# stm32f103c8t6.net
KiCad netlist of a schematic drawn in EasyEDA Pro
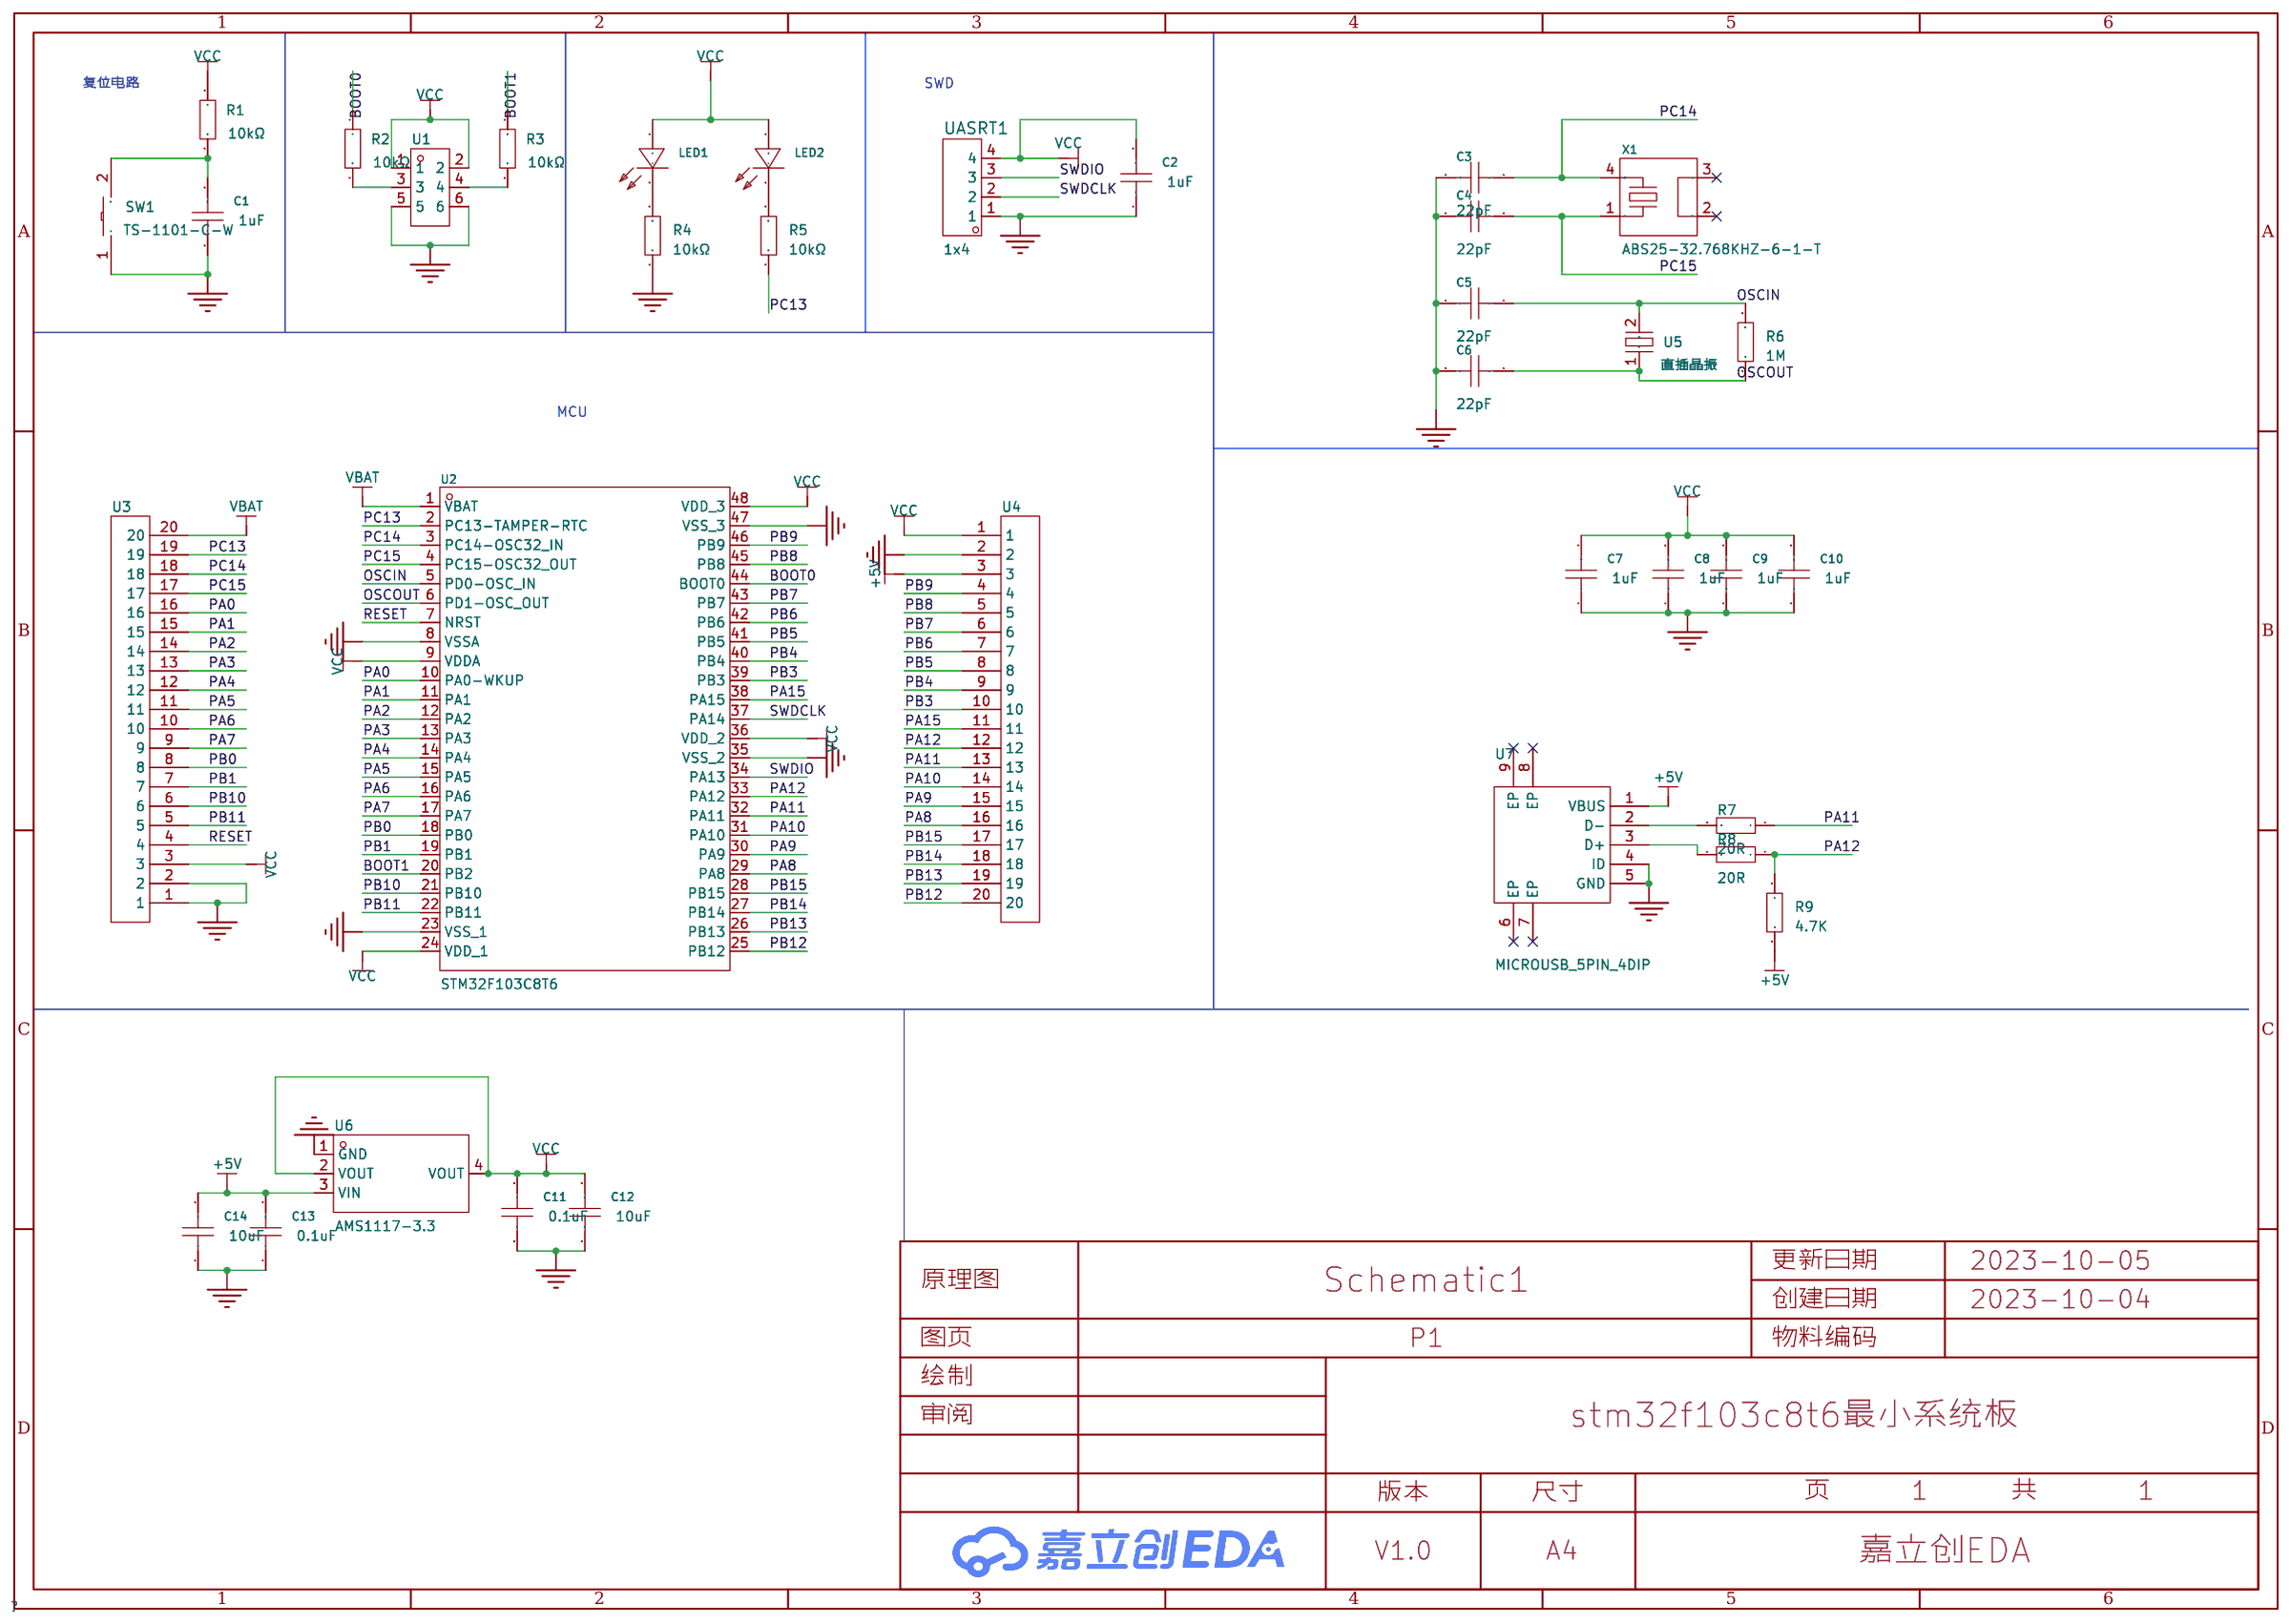
[diagram p0: schematic sheet]

(export (version "E")
  (design (tool "Eeschema 10.0.6"))
  (components
    (comp (ref "C1")
      (value "1uF")
      (footprint "easyedapro:C0603")
      (description "容值:4.7uF;额定电压:25V;材质(温度系数):X5R;")
      (fields
        (field (name "Manufacturer Part") "TCC0603X5R475K250CT")
        (field (name "Manufacturer") "CCTC(三环)")
      )
      (libsource (lib "easyedapro") (part "TCC0603X5R475K250CT"))
    )
    (comp (ref "C2")
      (value "1uF")
      (footprint "easyedapro:C0603")
      (description "容值:4.7uF;额定电压:25V;材质(温度系数):X5R;")
      (fields
        (field (name "Manufacturer Part") "TCC0603X5R475K250CT")
        (field (name "Manufacturer") "CCTC(三环)")
      )
      (libsource (lib "easyedapro") (part "TCC0603X5R475K250CT"))
    )
    (comp (ref "C3")
      (value "22pF")
      (footprint "easyedapro:C0603")
      (description "容值:4.7uF;额定电压:25V;材质(温度系数):X5R;")
      (fields
        (field (name "Manufacturer Part") "TCC0603X5R475K250CT")
        (field (name "Manufacturer") "CCTC(三环)")
      )
      (libsource (lib "easyedapro") (part "TCC0603X5R475K250CT"))
    )
    (comp (ref "C4")
      (value "22pF")
      (footprint "easyedapro:C0603")
      (description "容值:4.7uF;额定电压:25V;材质(温度系数):X5R;")
      (fields
        (field (name "Manufacturer Part") "TCC0603X5R475K250CT")
        (field (name "Manufacturer") "CCTC(三环)")
      )
      (libsource (lib "easyedapro") (part "TCC0603X5R475K250CT"))
    )
    (comp (ref "C5")
      (value "22pF")
      (footprint "easyedapro:C0603")
      (description "容值:4.7uF;额定电压:25V;材质(温度系数):X5R;")
      (fields
        (field (name "Manufacturer Part") "TCC0603X5R475K250CT")
        (field (name "Manufacturer") "CCTC(三环)")
      )
      (libsource (lib "easyedapro") (part "TCC0603X5R475K250CT"))
    )
    (comp (ref "C6")
      (value "22pF")
      (footprint "easyedapro:C0603")
      (description "容值:4.7uF;额定电压:25V;材质(温度系数):X5R;")
      (fields
        (field (name "Manufacturer Part") "TCC0603X5R475K250CT")
        (field (name "Manufacturer") "CCTC(三环)")
      )
      (libsource (lib "easyedapro") (part "TCC0603X5R475K250CT"))
    )
    (comp (ref "C7")
      (value "1uF")
      (footprint "easyedapro:C0603")
      (description "容值:4.7uF;额定电压:25V;材质(温度系数):X5R;")
      (fields
        (field (name "Manufacturer Part") "TCC0603X5R475K250CT")
        (field (name "Manufacturer") "CCTC(三环)")
      )
      (libsource (lib "easyedapro") (part "TCC0603X5R475K250CT"))
    )
    (comp (ref "C8")
      (value "1uF")
      (footprint "easyedapro:C0603")
      (description "容值:4.7uF;额定电压:25V;材质(温度系数):X5R;")
      (fields
        (field (name "Manufacturer Part") "TCC0603X5R475K250CT")
        (field (name "Manufacturer") "CCTC(三环)")
      )
      (libsource (lib "easyedapro") (part "TCC0603X5R475K250CT"))
    )
    (comp (ref "C9")
      (value "1uF")
      (footprint "easyedapro:C0603")
      (description "容值:4.7uF;额定电压:25V;材质(温度系数):X5R;")
      (fields
        (field (name "Manufacturer Part") "TCC0603X5R475K250CT")
        (field (name "Manufacturer") "CCTC(三环)")
      )
      (libsource (lib "easyedapro") (part "TCC0603X5R475K250CT"))
    )
    (comp (ref "C10")
      (value "1uF")
      (footprint "easyedapro:C0603")
      (description "容值:4.7uF;额定电压:25V;材质(温度系数):X5R;")
      (fields
        (field (name "Manufacturer Part") "TCC0603X5R475K250CT")
        (field (name "Manufacturer") "CCTC(三环)")
      )
      (libsource (lib "easyedapro") (part "TCC0603X5R475K250CT"))
    )
    (comp (ref "C11")
      (value "0.1uF")
      (footprint "easyedapro:C0603")
      (description "容值:4.7uF;额定电压:25V;材质(温度系数):X5R;")
      (fields
        (field (name "Manufacturer Part") "TCC0603X5R475K250CT")
        (field (name "Manufacturer") "CCTC(三环)")
      )
      (libsource (lib "easyedapro") (part "TCC0603X5R475K250CT"))
    )
    (comp (ref "C12")
      (value "10uF")
      (footprint "easyedapro:C0603")
      (description "容值:4.7uF;额定电压:25V;材质(温度系数):X5R;")
      (fields
        (field (name "Manufacturer Part") "TCC0603X5R475K250CT")
        (field (name "Manufacturer") "CCTC(三环)")
      )
      (libsource (lib "easyedapro") (part "TCC0603X5R475K250CT"))
    )
    (comp (ref "C13")
      (value "0.1uF")
      (footprint "easyedapro:C0603")
      (description "容值:4.7uF;额定电压:25V;材质(温度系数):X5R;")
      (fields
        (field (name "Manufacturer Part") "TCC0603X5R475K250CT")
        (field (name "Manufacturer") "CCTC(三环)")
      )
      (libsource (lib "easyedapro") (part "TCC0603X5R475K250CT"))
    )
    (comp (ref "C14")
      (value "10uF")
      (footprint "easyedapro:C0603")
      (description "容值:4.7uF;额定电压:25V;材质(温度系数):X5R;")
      (fields
        (field (name "Manufacturer Part") "TCC0603X5R475K250CT")
        (field (name "Manufacturer") "CCTC(三环)")
      )
      (libsource (lib "easyedapro") (part "TCC0603X5R475K250CT"))
    )
    (comp (ref "LED1")
      (value "KT-0805G")
      (footprint "easyedapro:LED0805-R-RD")
      (description "发光颜色:翠绿;二极管配置:-;透镜颜色:-;主波长:-;色温:-;光通量(25℃时):-;发光强度:-;功率:-;发光角度:-;安装方式:-;工作温度:-;")
      (fields (field (name "Manufacturer") "KENTO"))
      (libsource (lib "easyedapro") (part "0805G (Green)"))
    )
    (comp (ref "LED2")
      (value "KT-0805G")
      (footprint "easyedapro:LED0805-R-RD")
      (description "发光颜色:翠绿;二极管配置:-;透镜颜色:-;主波长:-;色温:-;光通量(25°C时):-;发光强度:-;功率:-;发光角度:-;安装方式:-;工作温度:-;")
      (fields (field (name "Manufacturer") "KENTO"))
      (libsource (lib "easyedapro") (part "0805G (Green)"))
    )
    (comp (ref "R1")
      (value "10kΩ")
      (footprint "easyedapro:R0603")
      (description "电阻类型:厚膜电阻;阻值:10kΩ;精度:±1%;功率:100mW;")
      (fields
        (field (name "Manufacturer Part") "0603WAF1002T5E")
        (field (name "Manufacturer") "UNI-ROYAL(厚声)")
      )
      (libsource (lib "easyedapro") (part "0603WAF1002T5E"))
    )
    (comp (ref "R2")
      (value "10kΩ")
      (footprint "easyedapro:R0603")
      (description "电阻类型:厚膜电阻;阻值:10kΩ;精度:±1%;功率:100mW;")
      (fields
        (field (name "Manufacturer Part") "0603WAF1002T5E")
        (field (name "Manufacturer") "UNI-ROYAL(厚声)")
      )
      (libsource (lib "easyedapro") (part "0603WAF1002T5E"))
    )
    (comp (ref "R3")
      (value "10kΩ")
      (footprint "easyedapro:R0603")
      (description "电阻类型:厚膜电阻;阻值:10kΩ;精度:±1%;功率:100mW;")
      (fields
        (field (name "Manufacturer Part") "0603WAF1002T5E")
        (field (name "Manufacturer") "UNI-ROYAL(厚声)")
      )
      (libsource (lib "easyedapro") (part "0603WAF1002T5E"))
    )
    (comp (ref "R4")
      (value "10kΩ")
      (footprint "easyedapro:R0603")
      (description "电阻类型:厚膜电阻;阻值:10kΩ;精度:±1%;功率:100mW;")
      (fields
        (field (name "Manufacturer Part") "0603WAF1002T5E")
        (field (name "Manufacturer") "UNI-ROYAL(厚声)")
      )
      (libsource (lib "easyedapro") (part "0603WAF1002T5E"))
    )
    (comp (ref "R5")
      (value "10kΩ")
      (footprint "easyedapro:R0603")
      (description "电阻类型:厚膜电阻;阻值:10kΩ;精度:±1%;功率:100mW;")
      (fields
        (field (name "Manufacturer Part") "0603WAF1002T5E")
        (field (name "Manufacturer") "UNI-ROYAL(厚声)")
      )
      (libsource (lib "easyedapro") (part "0603WAF1002T5E"))
    )
    (comp (ref "R6")
      (value "1M")
      (footprint "easyedapro:R0603")
      (description "电阻类型:厚膜电阻;阻值:10kΩ;精度:±1%;功率:100mW;")
      (fields
        (field (name "Manufacturer Part") "0603WAF1002T5E")
        (field (name "Manufacturer") "UNI-ROYAL(厚声)")
      )
      (libsource (lib "easyedapro") (part "0603WAF1002T5E"))
    )
    (comp (ref "R7")
      (value "20R")
      (footprint "easyedapro:R0603")
      (description "电阻类型:厚膜电阻;阻值:10kΩ;精度:±1%;功率:100mW;")
      (fields
        (field (name "Manufacturer Part") "0603WAF1002T5E")
        (field (name "Manufacturer") "UNI-ROYAL(厚声)")
      )
      (libsource (lib "easyedapro") (part "0603WAF1002T5E"))
    )
    (comp (ref "R8")
      (value "20R")
      (footprint "easyedapro:R0603")
      (description "电阻类型:厚膜电阻;阻值:10kΩ;精度:±1%;功率:100mW;")
      (fields
        (field (name "Manufacturer Part") "0603WAF1002T5E")
        (field (name "Manufacturer") "UNI-ROYAL(厚声)")
      )
      (libsource (lib "easyedapro") (part "0603WAF1002T5E"))
    )
    (comp (ref "R9")
      (value "4.7K")
      (footprint "easyedapro:R0603")
      (description "电阻类型:厚膜电阻;阻值:10kΩ;精度:±1%;功率:100mW;")
      (fields
        (field (name "Manufacturer Part") "0603WAF1002T5E")
        (field (name "Manufacturer") "UNI-ROYAL(厚声)")
      )
      (libsource (lib "easyedapro") (part "0603WAF1002T5E"))
    )
    (comp (ref "SW1")
      (value "TS-1101-C-W")
      (footprint "easyedapro:SW-SMD_L6.0-W3.3-LS8.0")
      (description "触点电流:50mA;额定电压(AC):-;额定电压(DC):12V;额定功率:-;绝缘电阻:-;电路结构:单刀单掷;安装方式:立贴;带灯:无;作用力:260gf;机械寿命:5万次;带支架:否;")
      (fields (field (name "Manufacturer") "XKB Connectivity(中国星坤)"))
      (libsource (lib "easyedapro") (part "TS-1101-C-W"))
    )
    (comp (ref "U1")
      (value "2.54mm,2X3,短针针长3mm,长针针长6mm")
      (footprint "easyedapro:HDR-TH_6P-P2.54-V-M-R2-C3-S2.54-2")
      (libsource (lib "easyedapro") (part "2.54MM,2X3,短针针长3MM,长针针长6MM"))
    )
    (comp (ref "U2")
      (value "STM32F103C8T6")
      (footprint "easyedapro:LQFP-48_L7.0-W7.0-P0.50-LS9.0-BL")
      (fields (field (name "Manufacturer") "ST(意法半导体)"))
      (libsource (lib "easyedapro") (part "STM32F103C8T6"))
    )
    (comp (ref "U3")
      (value "~")
      (footprint "easyedapro:HDR1X20")
      (libsource (lib "easyedapro") (part "1X20"))
    )
    (comp (ref "U4")
      (value "~")
      (footprint "easyedapro:HDR1X20")
      (libsource (lib "easyedapro") (part "1X20"))
    )
    (comp (ref "U5")
      (value "直插晶振")
      (footprint "easyedapro:HC-49S_L11.0-W4.7-P4.88")
      (libsource (lib "easyedapro") (part "直插晶振"))
    )
    (comp (ref "U6")
      (value "AMS1117-3.3")
      (footprint "easyedapro:SOT-223-3_L6.5-W3.4-P2.30-LS7.0-BR")
      (description "输出类型:固定;输出极性:正;最大输入电压:-;输出电压:3.3V;输出电流:1A;电源纹波抑制比(PSRR):72dB@(120Hz);")
      (fields (field (name "Manufacturer") "AMS"))
      (libsource (lib "easyedapro") (part "AMS1117-3.3"))
    )
    (comp (ref "U7")
      (value "MICROUSB_5PIN_4DIP")
      (footprint "easyedapro:MICRO-USB-SMD_U254-051N-4BH806")
      (libsource (lib "easyedapro") (part "MICROUSB_5PIN_4DIP"))
    )
    (comp (ref "UASRT1")
      (value "1x4")
      (footprint "easyedapro:HDR-TH_4P-P2.54-V-M-1")
      (fields
        (field (name "Manufacturer Part") "Headers  Pins 1*4P")
        (field (name "Manufacturer") "ReliaPro")
      )
      (libsource (lib "easyedapro") (part "1x4"))
    )
    (comp (ref "X1")
      (value "ABS25-32.768KHZ-6-1-T")
      (footprint "easyedapro:SOJ-4_L8.4-W3.8-P5.5-BL")
      (fields (field (name "Manufacturer") "ABRACON"))
      (libsource (lib "easyedapro") (part "ABS25-32.768KHZ-6-1-T"))
    )
  )
  (nets
    (net (code "1") (name "+5V") (class "Default")
      (node (ref "C13") (pin "2") (pinfunction "2_2") (pintype "input"))
      (node (ref "C14") (pin "2") (pinfunction "2_2") (pintype "input"))
      (node (ref "R9") (pin "2") (pinfunction "2_2") (pintype "input"))
      (node (ref "U4") (pin "3") (pinfunction "3_3") (pintype "input"))
      (node (ref "U6") (pin "3") (pinfunction "VIN_3") (pintype "input"))
      (node (ref "U7") (pin "1") (pinfunction "VBUS_1") (pintype "input"))
    )
    (net (code "2") (name "/BOOT0") (class "Default")
      (node (ref "R2") (pin "1") (pinfunction "1_1") (pintype "input"))
      (node (ref "U2") (pin "44") (pinfunction "BOOT0_44") (pintype "input"))
    )
    (net (code "3") (name "/BOOT1") (class "Default")
      (node (ref "R3") (pin "1") (pinfunction "1_1") (pintype "input"))
      (node (ref "U2") (pin "20") (pinfunction "PB2_20") (pintype "input"))
    )
    (net (code "4") (name "/OSCIN") (class "Default")
      (node (ref "C5") (pin "1") (pinfunction "1_1") (pintype "input"))
      (node (ref "R6") (pin "2") (pinfunction "2_2") (pintype "input"))
      (node (ref "U2") (pin "5") (pinfunction "PD0-OSC_IN_5") (pintype "input"))
      (node (ref "U5") (pin "2") (pinfunction "GND_2") (pintype "input"))
    )
    (net (code "5") (name "/OSCOUT") (class "Default")
      (node (ref "C6") (pin "1") (pinfunction "1_1") (pintype "input"))
      (node (ref "R6") (pin "1") (pinfunction "1_1") (pintype "input"))
      (node (ref "U2") (pin "6") (pinfunction "PD1-OSC_OUT_6") (pintype "input"))
      (node (ref "U5") (pin "1") (pinfunction "1_1") (pintype "input"))
    )
    (net (code "6") (name "/PA0") (class "Default")
      (node (ref "U2") (pin "10") (pinfunction "PA0-WKUP_10") (pintype "input"))
      (node (ref "U3") (pin "16") (pinfunction "16_16") (pintype "input"))
    )
    (net (code "7") (name "/PA1") (class "Default")
      (node (ref "U2") (pin "11") (pinfunction "PA1_11") (pintype "input"))
      (node (ref "U3") (pin "15") (pinfunction "15_15") (pintype "input"))
    )
    (net (code "8") (name "/PA2") (class "Default")
      (node (ref "U2") (pin "12") (pinfunction "PA2_12") (pintype "input"))
      (node (ref "U3") (pin "14") (pinfunction "14_14") (pintype "input"))
    )
    (net (code "9") (name "/PA3") (class "Default")
      (node (ref "U2") (pin "13") (pinfunction "PA3_13") (pintype "input"))
      (node (ref "U3") (pin "13") (pinfunction "13_13") (pintype "input"))
    )
    (net (code "10") (name "/PA4") (class "Default")
      (node (ref "U2") (pin "14") (pinfunction "PA4_14") (pintype "input"))
      (node (ref "U3") (pin "12") (pinfunction "12_12") (pintype "input"))
    )
    (net (code "11") (name "/PA5") (class "Default")
      (node (ref "U2") (pin "15") (pinfunction "PA5_15") (pintype "input"))
      (node (ref "U3") (pin "11") (pinfunction "11_11") (pintype "input"))
    )
    (net (code "12") (name "/PA6") (class "Default")
      (node (ref "U2") (pin "16") (pinfunction "PA6_16") (pintype "input"))
      (node (ref "U3") (pin "10") (pinfunction "10_10") (pintype "input"))
    )
    (net (code "13") (name "/PA7") (class "Default")
      (node (ref "U2") (pin "17") (pinfunction "PA7_17") (pintype "input"))
      (node (ref "U3") (pin "9") (pinfunction "9_9") (pintype "input"))
    )
    (net (code "14") (name "/PA8") (class "Default")
      (node (ref "U2") (pin "29") (pinfunction "PA8_29") (pintype "input"))
      (node (ref "U4") (pin "16") (pinfunction "16_16") (pintype "input"))
    )
    (net (code "15") (name "/PA9") (class "Default")
      (node (ref "U2") (pin "30") (pinfunction "PA9_30") (pintype "input"))
      (node (ref "U4") (pin "15") (pinfunction "15_15") (pintype "input"))
    )
    (net (code "16") (name "/PA10") (class "Default")
      (node (ref "U2") (pin "31") (pinfunction "PA10_31") (pintype "input"))
      (node (ref "U4") (pin "14") (pinfunction "14_14") (pintype "input"))
    )
    (net (code "17") (name "/PA11") (class "Default")
      (node (ref "R7") (pin "1") (pinfunction "1_1") (pintype "input"))
      (node (ref "U2") (pin "32") (pinfunction "PA11_32") (pintype "input"))
      (node (ref "U4") (pin "13") (pinfunction "13_13") (pintype "input"))
    )
    (net (code "18") (name "/PA12") (class "Default")
      (node (ref "R8") (pin "1") (pinfunction "1_1") (pintype "input"))
      (node (ref "R9") (pin "1") (pinfunction "1_1") (pintype "input"))
      (node (ref "U2") (pin "33") (pinfunction "PA12_33") (pintype "input"))
      (node (ref "U4") (pin "12") (pinfunction "12_12") (pintype "input"))
    )
    (net (code "19") (name "/PA15") (class "Default")
      (node (ref "U2") (pin "38") (pinfunction "PA15_38") (pintype "input"))
      (node (ref "U4") (pin "11") (pinfunction "11_11") (pintype "input"))
    )
    (net (code "20") (name "/PB0") (class "Default")
      (node (ref "U2") (pin "18") (pinfunction "PB0_18") (pintype "input"))
      (node (ref "U3") (pin "8") (pinfunction "8_8") (pintype "input"))
    )
    (net (code "21") (name "/PB1") (class "Default")
      (node (ref "U2") (pin "19") (pinfunction "PB1_19") (pintype "input"))
      (node (ref "U3") (pin "7") (pinfunction "7_7") (pintype "input"))
    )
    (net (code "22") (name "/PB3") (class "Default")
      (node (ref "U2") (pin "39") (pinfunction "PB3_39") (pintype "input"))
      (node (ref "U4") (pin "10") (pinfunction "10_10") (pintype "input"))
    )
    (net (code "23") (name "/PB4") (class "Default")
      (node (ref "U2") (pin "40") (pinfunction "PB4_40") (pintype "input"))
      (node (ref "U4") (pin "9") (pinfunction "9_9") (pintype "input"))
    )
    (net (code "24") (name "/PB5") (class "Default")
      (node (ref "U2") (pin "41") (pinfunction "PB5_41") (pintype "input"))
      (node (ref "U4") (pin "8") (pinfunction "8_8") (pintype "input"))
    )
    (net (code "25") (name "/PB6") (class "Default")
      (node (ref "U2") (pin "42") (pinfunction "PB6_42") (pintype "input"))
      (node (ref "U4") (pin "7") (pinfunction "7_7") (pintype "input"))
    )
    (net (code "26") (name "/PB7") (class "Default")
      (node (ref "U2") (pin "43") (pinfunction "PB7_43") (pintype "input"))
      (node (ref "U4") (pin "6") (pinfunction "6_6") (pintype "input"))
    )
    (net (code "27") (name "/PB8") (class "Default")
      (node (ref "U2") (pin "45") (pinfunction "PB8_45") (pintype "input"))
      (node (ref "U4") (pin "5") (pinfunction "5_5") (pintype "input"))
    )
    (net (code "28") (name "/PB9") (class "Default")
      (node (ref "U2") (pin "46") (pinfunction "PB9_46") (pintype "input"))
      (node (ref "U4") (pin "4") (pinfunction "4_4") (pintype "input"))
    )
    (net (code "29") (name "/PB10") (class "Default")
      (node (ref "U2") (pin "21") (pinfunction "PB10_21") (pintype "input"))
      (node (ref "U3") (pin "6") (pinfunction "6_6") (pintype "input"))
    )
    (net (code "30") (name "/PB11") (class "Default")
      (node (ref "U2") (pin "22") (pinfunction "PB11_22") (pintype "input"))
      (node (ref "U3") (pin "5") (pinfunction "5_5") (pintype "input"))
    )
    (net (code "31") (name "/PB12") (class "Default")
      (node (ref "U2") (pin "25") (pinfunction "PB12_25") (pintype "input"))
      (node (ref "U4") (pin "20") (pinfunction "20_20") (pintype "input"))
    )
    (net (code "32") (name "/PB13") (class "Default")
      (node (ref "U2") (pin "26") (pinfunction "PB13_26") (pintype "input"))
      (node (ref "U4") (pin "19") (pinfunction "19_19") (pintype "input"))
    )
    (net (code "33") (name "/PB14") (class "Default")
      (node (ref "U2") (pin "27") (pinfunction "PB14_27") (pintype "input"))
      (node (ref "U4") (pin "18") (pinfunction "18_18") (pintype "input"))
    )
    (net (code "34") (name "/PB15") (class "Default")
      (node (ref "U2") (pin "28") (pinfunction "PB15_28") (pintype "input"))
      (node (ref "U4") (pin "17") (pinfunction "17_17") (pintype "input"))
    )
    (net (code "35") (name "/PC13") (class "Default")
      (node (ref "R5") (pin "1") (pinfunction "1_1") (pintype "input"))
      (node (ref "U2") (pin "2") (pinfunction "PC13-TAMPER-RTC_2") (pintype "input"))
      (node (ref "U3") (pin "19") (pinfunction "19_19") (pintype "input"))
    )
    (net (code "36") (name "/PC14") (class "Default")
      (node (ref "C3") (pin "1") (pinfunction "1_1") (pintype "input"))
      (node (ref "U2") (pin "3") (pinfunction "PC14-OSC32_IN_3") (pintype "input"))
      (node (ref "U3") (pin "18") (pinfunction "18_18") (pintype "input"))
      (node (ref "X1") (pin "4") (pinfunction "GND_4") (pintype "input"))
    )
    (net (code "37") (name "/PC15") (class "Default")
      (node (ref "C4") (pin "1") (pinfunction "1_1") (pintype "input"))
      (node (ref "U2") (pin "4") (pinfunction "PC15-OSC32_OUT_4") (pintype "input"))
      (node (ref "U3") (pin "17") (pinfunction "17_17") (pintype "input"))
      (node (ref "X1") (pin "1") (pinfunction "1_1") (pintype "input"))
    )
    (net (code "38") (name "/RESET") (class "Default")
      (node (ref "U2") (pin "7") (pinfunction "NRST_7") (pintype "input"))
      (node (ref "U3") (pin "4") (pinfunction "4_4") (pintype "input"))
    )
    (net (code "39") (name "/SWDCLK") (class "Default")
      (node (ref "U2") (pin "37") (pinfunction "PA14_37") (pintype "input"))
      (node (ref "UASRT1") (pin "2") (pinfunction "2_2") (pintype "input"))
    )
    (net (code "40") (name "/SWDIO") (class "Default")
      (node (ref "U2") (pin "34") (pinfunction "PA13_34") (pintype "input"))
      (node (ref "UASRT1") (pin "3") (pinfunction "3_3") (pintype "input"))
    )
    (net (code "41") (name "GND") (class "Default")
      (node (ref "C1") (pin "1") (pinfunction "1_1") (pintype "input"))
      (node (ref "C10") (pin "1") (pinfunction "1_1") (pintype "input"))
      (node (ref "C11") (pin "1") (pinfunction "1_1") (pintype "input"))
      (node (ref "C12") (pin "1") (pinfunction "1_1") (pintype "input"))
      (node (ref "C13") (pin "1") (pinfunction "1_1") (pintype "input"))
      (node (ref "C14") (pin "1") (pinfunction "1_1") (pintype "input"))
      (node (ref "C2") (pin "1") (pinfunction "1_1") (pintype "input"))
      (node (ref "C3") (pin "2") (pinfunction "2_2") (pintype "input"))
      (node (ref "C4") (pin "2") (pinfunction "2_2") (pintype "input"))
      (node (ref "C5") (pin "2") (pinfunction "2_2") (pintype "input"))
      (node (ref "C6") (pin "2") (pinfunction "2_2") (pintype "input"))
      (node (ref "C7") (pin "1") (pinfunction "1_1") (pintype "input"))
      (node (ref "C8") (pin "1") (pinfunction "1_1") (pintype "input"))
      (node (ref "C9") (pin "1") (pinfunction "1_1") (pintype "input"))
      (node (ref "R4") (pin "1") (pinfunction "1_1") (pintype "input"))
      (node (ref "SW1") (pin "1") (pinfunction "1_1") (pintype "input"))
      (node (ref "U1") (pin "5") (pinfunction "5_5") (pintype "input"))
      (node (ref "U1") (pin "6") (pinfunction "6_6") (pintype "input"))
      (node (ref "U2") (pin "23") (pinfunction "VSS_1_23") (pintype "input"))
      (node (ref "U2") (pin "35") (pinfunction "VSS_2_35") (pintype "input"))
      (node (ref "U2") (pin "47") (pinfunction "VSS_3_47") (pintype "input"))
      (node (ref "U2") (pin "8") (pinfunction "VSSA_8") (pintype "input"))
      (node (ref "U3") (pin "1") (pinfunction "1_1") (pintype "input"))
      (node (ref "U3") (pin "2") (pinfunction "2_2") (pintype "input"))
      (node (ref "U4") (pin "2") (pinfunction "2_2") (pintype "input"))
      (node (ref "U6") (pin "1") (pinfunction "GND_1") (pintype "input"))
      (node (ref "U7") (pin "4") (pinfunction "ID_4") (pintype "input"))
      (node (ref "U7") (pin "5") (pinfunction "GND_5") (pintype "input"))
      (node (ref "UASRT1") (pin "1") (pinfunction "1_1") (pintype "input"))
    )
    (net (code "42") (name "Net-(C1-Pad2)") (class "Default")
      (node (ref "C1") (pin "2") (pinfunction "2_2") (pintype "input"))
      (node (ref "R1") (pin "2") (pinfunction "2_2") (pintype "input"))
      (node (ref "SW1") (pin "2") (pinfunction "2_2") (pintype "input"))
    )
    (net (code "43") (name "Net-(LED1-K)") (class "Default")
      (node (ref "LED1") (pin "2") (pinfunction "K_2") (pintype "input"))
      (node (ref "R4") (pin "2") (pinfunction "2_2") (pintype "input"))
    )
    (net (code "44") (name "Net-(LED2-K)") (class "Default")
      (node (ref "LED2") (pin "2") (pinfunction "K_2") (pintype "input"))
      (node (ref "R5") (pin "2") (pinfunction "2_2") (pintype "input"))
    )
    (net (code "45") (name "Net-(R2-Pad2)") (class "Default")
      (node (ref "R2") (pin "2") (pinfunction "2_2") (pintype "input"))
      (node (ref "U1") (pin "3") (pinfunction "3_3") (pintype "input"))
    )
    (net (code "46") (name "Net-(R3-Pad2)") (class "Default")
      (node (ref "R3") (pin "2") (pinfunction "2_2") (pintype "input"))
      (node (ref "U1") (pin "4") (pinfunction "4_4") (pintype "input"))
    )
    (net (code "47") (name "Net-(U7-D+)") (class "Default")
      (node (ref "R8") (pin "2") (pinfunction "2_2") (pintype "input"))
      (node (ref "U7") (pin "3") (pinfunction "D+_3") (pintype "input"))
    )
    (net (code "48") (name "Net-(U7-D-)") (class "Default")
      (node (ref "R7") (pin "2") (pinfunction "2_2") (pintype "input"))
      (node (ref "U7") (pin "2") (pinfunction "D-_2") (pintype "input"))
    )
    (net (code "49") (name "VBAT") (class "Default")
      (node (ref "U2") (pin "1") (pinfunction "VBAT_1") (pintype "input"))
      (node (ref "U3") (pin "20") (pinfunction "20_20") (pintype "input"))
    )
    (net (code "50") (name "VCC") (class "Default")
      (node (ref "C10") (pin "2") (pinfunction "2_2") (pintype "input"))
      (node (ref "C11") (pin "2") (pinfunction "2_2") (pintype "input"))
      (node (ref "C12") (pin "2") (pinfunction "2_2") (pintype "input"))
      (node (ref "C2") (pin "2") (pinfunction "2_2") (pintype "input"))
      (node (ref "C7") (pin "2") (pinfunction "2_2") (pintype "input"))
      (node (ref "C8") (pin "2") (pinfunction "2_2") (pintype "input"))
      (node (ref "C9") (pin "2") (pinfunction "2_2") (pintype "input"))
      (node (ref "LED1") (pin "1") (pinfunction "A_1") (pintype "input"))
      (node (ref "LED2") (pin "1") (pinfunction "A_1") (pintype "input"))
      (node (ref "R1") (pin "1") (pinfunction "1_1") (pintype "input"))
      (node (ref "U1") (pin "1") (pinfunction "1_1") (pintype "input"))
      (node (ref "U1") (pin "2") (pinfunction "2_2") (pintype "input"))
      (node (ref "U2") (pin "24") (pinfunction "VDD_1_24") (pintype "input"))
      (node (ref "U2") (pin "36") (pinfunction "VDD_2_36") (pintype "input"))
      (node (ref "U2") (pin "48") (pinfunction "VDD_3_48") (pintype "input"))
      (node (ref "U2") (pin "9") (pinfunction "VDDA_9") (pintype "input"))
      (node (ref "U3") (pin "3") (pinfunction "3_3") (pintype "input"))
      (node (ref "U4") (pin "1") (pinfunction "1_1") (pintype "input"))
      (node (ref "U6") (pin "2") (pinfunction "VOUT_2") (pintype "input"))
      (node (ref "U6") (pin "4") (pinfunction "VOUT_4") (pintype "input"))
      (node (ref "UASRT1") (pin "4") (pinfunction "4_4") (pintype "input"))
    )
    (net (code "51") (name "unconnected-(U7-EP-Pad6)") (class "Default")
      (node (ref "U7") (pin "6") (pinfunction "EP_6") (pintype "input+no_connect"))
    )
    (net (code "52") (name "unconnected-(U7-EP-Pad7)") (class "Default")
      (node (ref "U7") (pin "7") (pinfunction "EP_7") (pintype "input+no_connect"))
    )
    (net (code "53") (name "unconnected-(U7-EP-Pad8)") (class "Default")
      (node (ref "U7") (pin "8") (pinfunction "EP_8") (pintype "input+no_connect"))
    )
    (net (code "54") (name "unconnected-(U7-EP-Pad9)") (class "Default")
      (node (ref "U7") (pin "9") (pinfunction "EP_9") (pintype "input+no_connect"))
    )
    (net (code "55") (name "unconnected-(X1-GND-Pad2)") (class "Default")
      (node (ref "X1") (pin "2") (pinfunction "GND_2") (pintype "input+no_connect"))
    )
    (net (code "56") (name "unconnected-(X1-Pad3)") (class "Default")
      (node (ref "X1") (pin "3") (pinfunction "3_3") (pintype "input+no_connect"))
    )
  )
)
